# Sensors.net
KiCad netlist of a schematic drawn in Altium Designer
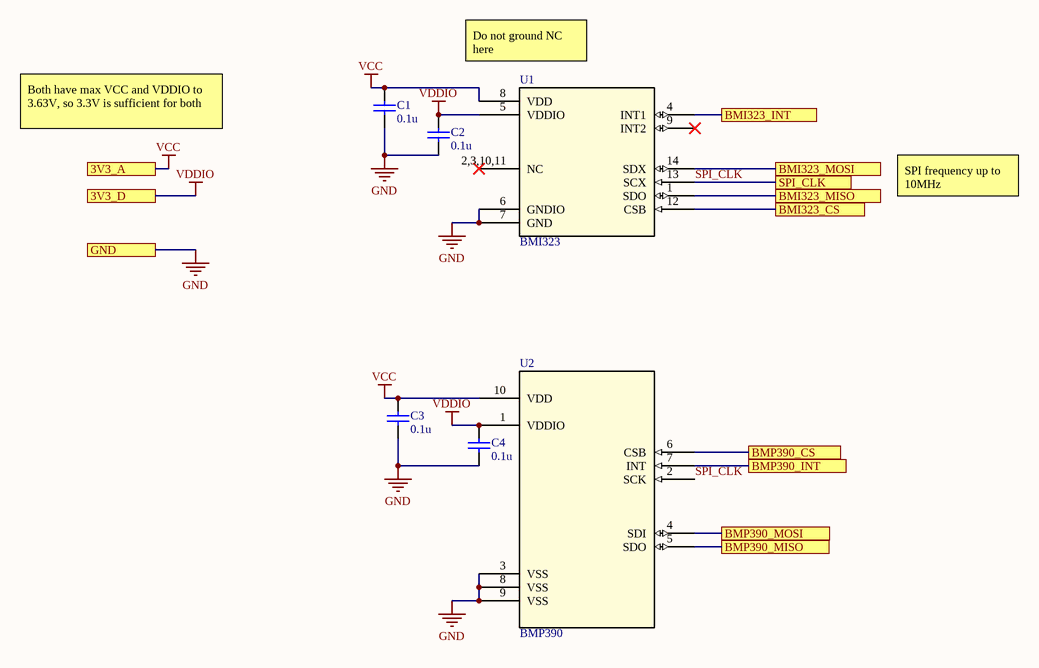
[diagram p0: Sensors.SchDoc]

(export (version "E")
  (design (tool "Eeschema 10.0.6"))
  (components
    (comp (ref "C1")
      (value "0.1u")
      (description "Capacitor")
      (libsource (lib "Simulation Generic Components") (part "Capacitor"))
    )
    (comp (ref "C2")
      (value "0.1u")
      (description "Capacitor")
      (libsource (lib "Simulation Generic Components") (part "Capacitor"))
    )
    (comp (ref "C3")
      (value "0.1u")
      (description "Capacitor")
      (libsource (lib "Simulation Generic Components") (part "Capacitor"))
    )
    (comp (ref "C4")
      (value "0.1u")
      (description "Capacitor")
      (libsource (lib "Simulation Generic Components") (part "Capacitor"))
    )
    (comp (ref "U1")
      (value "BMI323")
      (footprint "BMI323_BOS")
      (description "Description")
      (fields (field (name "COPYRIGHT") "Copyright (C) 2025 Ultra Librarian. All rights reserved."))
      (libsource (lib "BMI323") (part "BMI323"))
    )
    (comp (ref "U2")
      (value "BMP390")
      (footprint "10LGA_2X2X0p75_BOS")
      (description "Description")
      (fields (field (name "COPYRIGHT") "Copyright (C) 2025 Ultra Librarian. All rights reserved."))
      (libsource (lib "BMP390") (part "BMP390"))
    )
  )
  (nets
    (net (code "1") (name "/BMI323_CS") (class "Default")
      (node (ref "U1") (pin "12") (pinfunction "CSB_12") (pintype "input"))
    )
    (net (code "2") (name "/BMI323_INT") (class "Default")
      (node (ref "U1") (pin "4") (pinfunction "INT1_4") (pintype "bidirectional"))
    )
    (net (code "3") (name "/BMI323_MISO") (class "Default")
      (node (ref "U1") (pin "1") (pinfunction "SDO_1") (pintype "bidirectional"))
    )
    (net (code "4") (name "/BMI323_MOSI") (class "Default")
      (node (ref "U1") (pin "14") (pinfunction "SDX_14") (pintype "bidirectional"))
    )
    (net (code "5") (name "/BMP390_CS") (class "Default")
      (node (ref "U2") (pin "6") (pinfunction "CSB_6") (pintype "input"))
    )
    (net (code "6") (name "/BMP390_INT") (class "Default")
      (node (ref "U2") (pin "7") (pinfunction "INT_7") (pintype "input"))
    )
    (net (code "7") (name "/BMP390_MISO") (class "Default")
      (node (ref "U2") (pin "5") (pinfunction "SDO_5") (pintype "bidirectional"))
    )
    (net (code "8") (name "/BMP390_MOSI") (class "Default")
      (node (ref "U2") (pin "4") (pinfunction "SDI_4") (pintype "bidirectional"))
    )
    (net (code "9") (name "/SPI_CLK") (class "Default")
      (node (ref "U1") (pin "13") (pinfunction "SCX_13") (pintype "input"))
      (node (ref "U2") (pin "2") (pinfunction "SCK_2") (pintype "input"))
    )
    (net (code "10") (name "GND") (class "Default")
      (node (ref "C1") (pin "1") (pinfunction "1_1") (pintype "passive"))
      (node (ref "C2") (pin "1") (pinfunction "1_1") (pintype "passive"))
      (node (ref "C3") (pin "1") (pinfunction "1_1") (pintype "passive"))
      (node (ref "C4") (pin "1") (pinfunction "1_1") (pintype "passive"))
      (node (ref "U1") (pin "6") (pinfunction "GNDIO_6") (pintype "power_in"))
      (node (ref "U1") (pin "7") (pinfunction "GND_7") (pintype "power_in"))
      (node (ref "U2") (pin "3") (pinfunction "VSS_3") (pintype "power_in"))
      (node (ref "U2") (pin "8") (pinfunction "VSS_8") (pintype "power_in"))
      (node (ref "U2") (pin "9") (pinfunction "VSS_9") (pintype "power_in"))
    )
    (net (code "11") (name "VCC") (class "Default")
      (node (ref "C1") (pin "2") (pinfunction "2_2") (pintype "passive"))
      (node (ref "C3") (pin "2") (pinfunction "2_2") (pintype "passive"))
      (node (ref "U1") (pin "8") (pinfunction "VDD_8") (pintype "power_in"))
      (node (ref "U2") (pin "10") (pinfunction "VDD_10") (pintype "power_in"))
    )
    (net (code "12") (name "VDDIO") (class "Default")
      (node (ref "C2") (pin "2") (pinfunction "2_2") (pintype "passive"))
      (node (ref "C4") (pin "2") (pinfunction "2_2") (pintype "passive"))
      (node (ref "U1") (pin "5") (pinfunction "VDDIO_5") (pintype "power_in"))
      (node (ref "U2") (pin "1") (pinfunction "VDDIO_1") (pintype "power_in"))
    )
    (net (code "13") (name "unconnected-(U1-INT2-Pad9)") (class "Default")
      (node (ref "U1") (pin "9") (pinfunction "INT2_9") (pintype "bidirectional+no_connect"))
    )
    (net (code "14") (name "unconnected-(U1-NC-Pad2)") (class "Default")
      (node (ref "U1") (pin "2") (pinfunction "NC_2") (pintype "passive+no_connect"))
      (node (ref "U1") (pin "3") (pinfunction "NC_3") (pintype "passive+no_connect"))
      (node (ref "U1") (pin "10") (pinfunction "NC_10") (pintype "passive+no_connect"))
      (node (ref "U1") (pin "11") (pinfunction "NC_11") (pintype "passive+no_connect"))
    )
  )
)
